# Power_Outlet-RevB.net
KiCad netlist of a schematic drawn in EAGLE
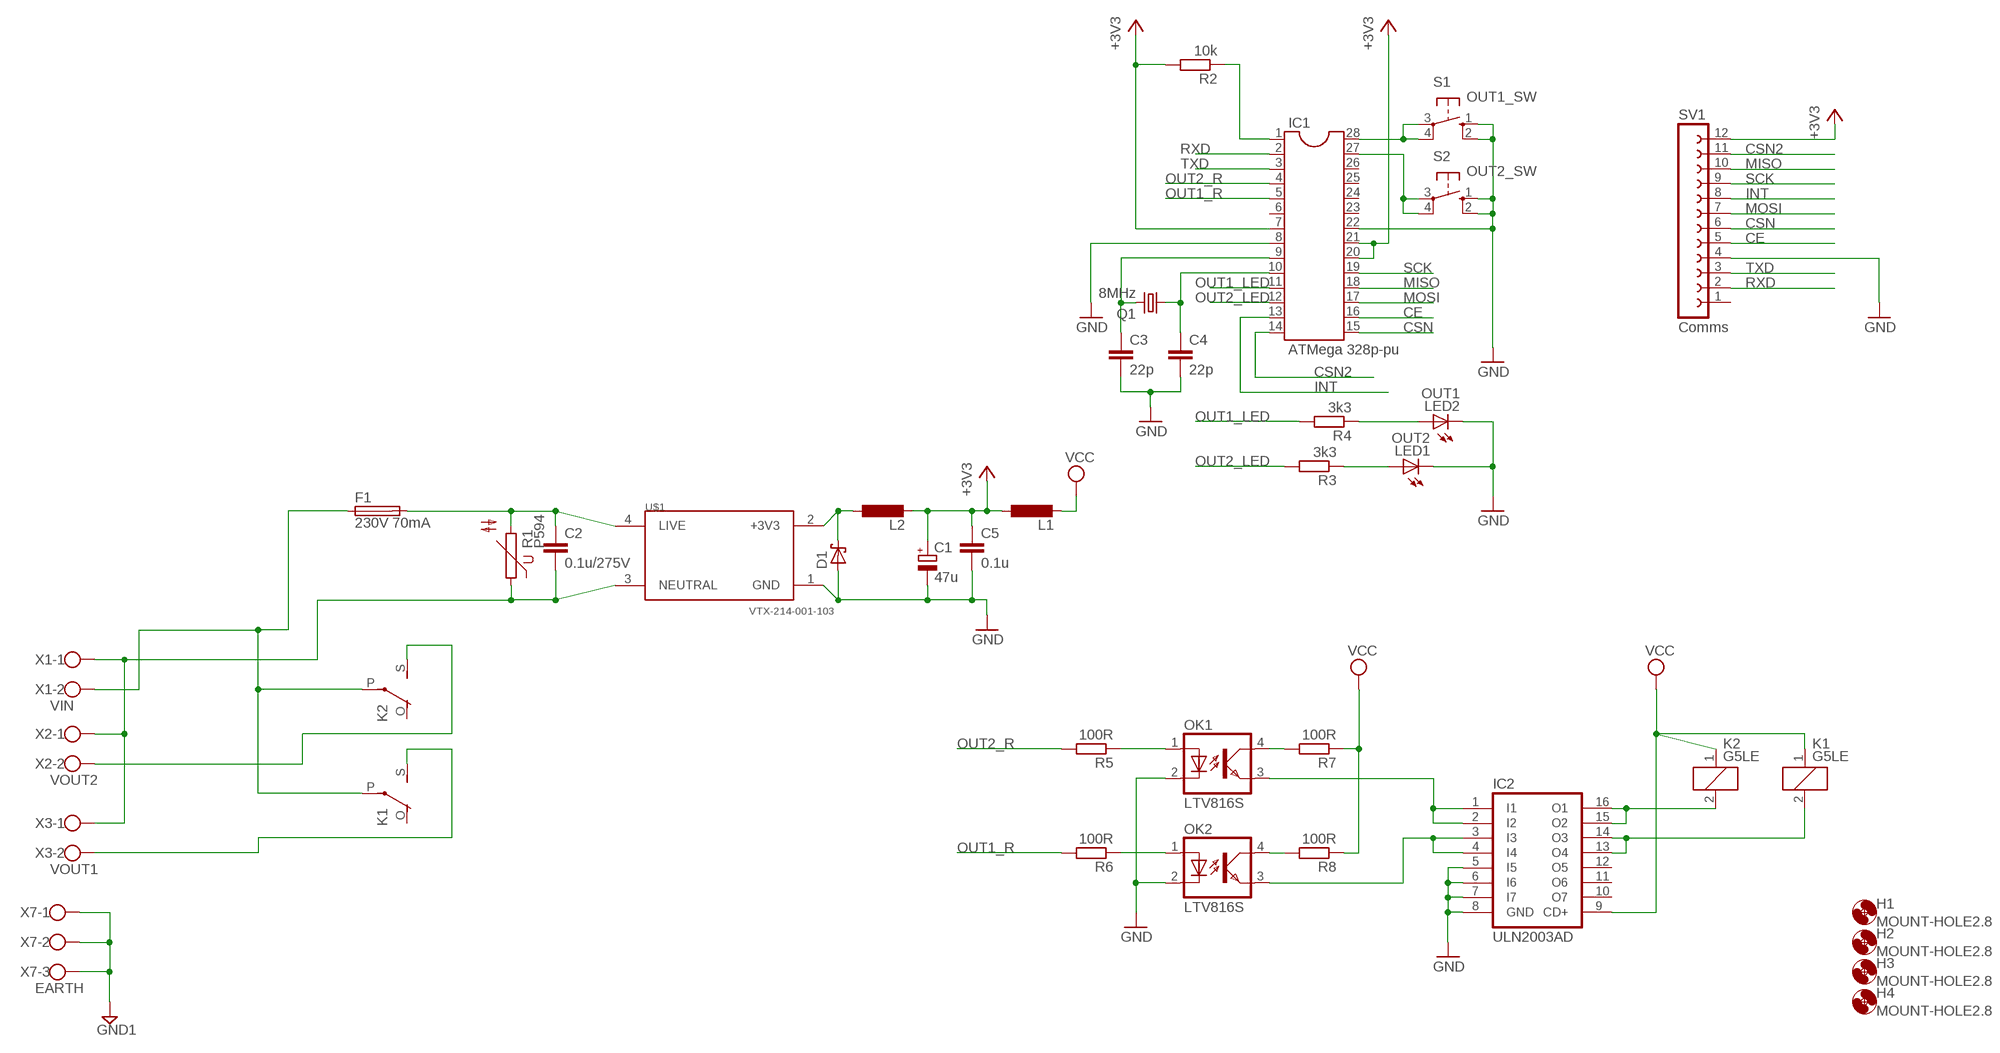
[diagram p0: schematic, sheet 1]

(export (version "E")
  (design (tool "Eeschema 10.0.6"))
  (components
    (comp (ref "C1")
      (value "47u")
      (footprint "eagle-import:E2,5-6E")
      (libsource (lib "eagle-import") (part "CPOL-EUE2,5-6E"))
    )
    (comp (ref "C2")
      (value "0.1u/275V")
      (footprint "eagle-import:C150-054X183")
      (libsource (lib "eagle-import") (part "C-EU150-054X183"))
    )
    (comp (ref "C3")
      (value "22p")
      (footprint "eagle-import:C1206K")
      (libsource (lib "eagle-import") (part "C-EUC1206K"))
    )
    (comp (ref "C4")
      (value "22p")
      (footprint "eagle-import:C1206K")
      (libsource (lib "eagle-import") (part "C-EUC1206K"))
    )
    (comp (ref "C5")
      (value "0.1u")
      (footprint "eagle-import:C1206K")
      (libsource (lib "eagle-import") (part "C-EUC1206K"))
    )
    (comp (ref "D1")
      (value "SCHOTTKY-DIODESMC")
      (footprint "eagle-import:SMC")
      (libsource (lib "eagle-import") (part "SCHOTTKY-DIODESMC"))
    )
    (comp (ref "F1")
      (value "230V 70mA")
      (footprint "eagle-import:SH22,5A")
      (libsource (lib "eagle-import") (part "FUSESH22,5A"))
    )
    (comp (ref "H1")
      (value "MOUNT-HOLE2.8")
      (footprint "eagle-import:2,8")
      (libsource (lib "eagle-import") (part "MOUNT-HOLE2.8"))
    )
    (comp (ref "H2")
      (value "MOUNT-HOLE2.8")
      (footprint "eagle-import:2,8")
      (libsource (lib "eagle-import") (part "MOUNT-HOLE2.8"))
    )
    (comp (ref "H3")
      (value "MOUNT-HOLE2.8")
      (footprint "eagle-import:2,8")
      (libsource (lib "eagle-import") (part "MOUNT-HOLE2.8"))
    )
    (comp (ref "H4")
      (value "MOUNT-HOLE2.8")
      (footprint "eagle-import:2,8")
      (libsource (lib "eagle-import") (part "MOUNT-HOLE2.8"))
    )
    (comp (ref "IC1")
      (value "ATMega 328p-pu")
      (footprint "eagle-import:DIL28-3")
      (libsource (lib "eagle-import") (part "DIL28-3"))
    )
    (comp (ref "IC2")
      (value "ULN2003AD")
      (footprint "eagle-import:SO16")
      (libsource (lib "eagle-import") (part "ULN2003AD"))
    )
    (comp (ref "K1")
      (value "G5LE")
      (footprint "eagle-import:G5LE")
      (libsource (lib "eagle-import") (part "G5LE"))
    )
    (comp (ref "K2")
      (value "G5LE")
      (footprint "eagle-import:G5LE")
      (libsource (lib "eagle-import") (part "G5LE"))
    )
    (comp (ref "L1")
      (value "L-EUL3225P")
      (footprint "eagle-import:L3225P")
      (libsource (lib "eagle-import") (part "L-EUL3225P"))
    )
    (comp (ref "L2")
      (value "L-EUL3225P")
      (footprint "eagle-import:L3225P")
      (libsource (lib "eagle-import") (part "L-EUL3225P"))
    )
    (comp (ref "LED1")
      (value "OUT2")
      (footprint "eagle-import:LED5MM")
      (libsource (lib "eagle-import") (part "LED5MM"))
    )
    (comp (ref "LED2")
      (value "OUT1")
      (footprint "eagle-import:LED5MM")
      (libsource (lib "eagle-import") (part "LED5MM"))
    )
    (comp (ref "OK1")
      (value "LTV816S")
      (footprint "eagle-import:DIL4-SMD")
      (libsource (lib "eagle-import") (part "LTV816S"))
    )
    (comp (ref "OK2")
      (value "LTV816S")
      (footprint "eagle-import:DIL4-SMD")
      (libsource (lib "eagle-import") (part "LTV816S"))
    )
    (comp (ref "Q1")
      (value "8MHz")
      (footprint "eagle-import:HC49_S")
      (libsource (lib "eagle-import") (part "CRYSTALHC49S"))
    )
    (comp (ref "R1")
      (value "P594")
      (footprint "eagle-import:P594")
      (libsource (lib "eagle-import") (part "P594"))
    )
    (comp (ref "R2")
      (value "10k")
      (footprint "eagle-import:R1206W")
      (libsource (lib "eagle-import") (part "R-EU_R1206W"))
    )
    (comp (ref "R3")
      (value "3k3")
      (footprint "eagle-import:R1206W")
      (libsource (lib "eagle-import") (part "R-EU_R1206W"))
    )
    (comp (ref "R4")
      (value "3k3")
      (footprint "eagle-import:R1206W")
      (libsource (lib "eagle-import") (part "R-EU_R1206W"))
    )
    (comp (ref "R5")
      (value "100R")
      (footprint "eagle-import:R1206W")
      (libsource (lib "eagle-import") (part "R-EU_R1206W"))
    )
    (comp (ref "R6")
      (value "100R")
      (footprint "eagle-import:R1206W")
      (libsource (lib "eagle-import") (part "R-EU_R1206W"))
    )
    (comp (ref "R7")
      (value "100R")
      (footprint "eagle-import:R1206W")
      (libsource (lib "eagle-import") (part "R-EU_R1206W"))
    )
    (comp (ref "R8")
      (value "100R")
      (footprint "eagle-import:R1206W")
      (libsource (lib "eagle-import") (part "R-EU_R1206W"))
    )
    (comp (ref "S1")
      (value "OUT1_SW")
      (footprint "eagle-import:B3F-40XX")
      (fields (field (name "MF") "OMRON COMPONENTS USA") (field (name "MPN") "B3F-4000"))
      (libsource (lib "eagle-import") (part "40-XX"))
    )
    (comp (ref "S2")
      (value "OUT2_SW")
      (footprint "eagle-import:B3F-40XX")
      (fields (field (name "MF") "OMRON COMPONENTS USA") (field (name "MPN") "B3F-4000"))
      (libsource (lib "eagle-import") (part "40-XX"))
    )
    (comp (ref "SV1")
      (value "Comms")
      (footprint "eagle-import:FE12W")
      (libsource (lib "eagle-import") (part "FE12W"))
    )
    (comp (ref "U$1")
      (value "VTX-214-001-103")
      (footprint "eagle-import:VTX214001103")
      (libsource (lib "eagle-import") (part "VTX-214-001-103"))
    )
    (comp (ref "X1")
      (value "VIN")
      (footprint "eagle-import:W237-102")
      (fields (field (name "MPN") "237-102"))
      (libsource (lib "eagle-import") (part "W237-102"))
    )
    (comp (ref "X2")
      (value "VOUT2")
      (footprint "eagle-import:W237-102")
      (fields (field (name "MPN") "237-102"))
      (libsource (lib "eagle-import") (part "W237-102"))
    )
    (comp (ref "X3")
      (value "VOUT1")
      (footprint "eagle-import:W237-102")
      (fields (field (name "MPN") "237-102"))
      (libsource (lib "eagle-import") (part "W237-102"))
    )
    (comp (ref "X7")
      (value "EARTH")
      (footprint "eagle-import:W237-103")
      (fields (field (name "MPN") "237-103"))
      (libsource (lib "eagle-import") (part "W237-103"))
    )
  )
  (nets
    (net (code "1") (name "+3V3") (class "Default")
      (node (ref "C1") (pin "+") (pinfunction "+_+") (pintype "passive"))
      (node (ref "C5") (pin "1") (pinfunction "1_1") (pintype "passive"))
      (node (ref "D1") (pin "C") (pinfunction "C_C") (pintype "passive"))
      (node (ref "IC1") (pin "20") (pinfunction "20_20") (pintype "passive"))
      (node (ref "IC1") (pin "21") (pinfunction "21_21") (pintype "passive"))
      (node (ref "IC1") (pin "7") (pinfunction "7_7") (pintype "passive"))
      (node (ref "L1") (pin "1") (pinfunction "1_1") (pintype "passive"))
      (node (ref "L2") (pin "1") (pinfunction "1_1") (pintype "passive"))
      (node (ref "L2") (pin "2") (pinfunction "2_2") (pintype "passive"))
      (node (ref "R2") (pin "2") (pinfunction "2_2") (pintype "passive"))
      (node (ref "SV1") (pin "12") (pinfunction "12_12") (pintype "passive"))
      (node (ref "U$1") (pin "2") (pinfunction "+3V3_2") (pintype "power_in"))
    )
    (net (code "2") (name "/CE") (class "Default")
      (node (ref "IC1") (pin "16") (pinfunction "16_16") (pintype "passive"))
      (node (ref "SV1") (pin "5") (pinfunction "5_5") (pintype "passive"))
    )
    (net (code "3") (name "/CSN") (class "Default")
      (node (ref "IC1") (pin "15") (pinfunction "15_15") (pintype "passive"))
      (node (ref "SV1") (pin "6") (pinfunction "6_6") (pintype "passive"))
    )
    (net (code "4") (name "/CSN2") (class "Default")
      (node (ref "IC1") (pin "14") (pinfunction "14_14") (pintype "passive"))
      (node (ref "SV1") (pin "11") (pinfunction "11_11") (pintype "passive"))
    )
    (net (code "5") (name "/INT") (class "Default")
      (node (ref "IC1") (pin "13") (pinfunction "13_13") (pintype "passive"))
      (node (ref "SV1") (pin "8") (pinfunction "8_8") (pintype "passive"))
    )
    (net (code "6") (name "/MISO") (class "Default")
      (node (ref "IC1") (pin "18") (pinfunction "18_18") (pintype "passive"))
      (node (ref "SV1") (pin "10") (pinfunction "10_10") (pintype "passive"))
    )
    (net (code "7") (name "/MOSI") (class "Default")
      (node (ref "IC1") (pin "17") (pinfunction "17_17") (pintype "passive"))
      (node (ref "SV1") (pin "7") (pinfunction "7_7") (pintype "passive"))
    )
    (net (code "8") (name "/OUT1_LED") (class "Default")
      (node (ref "IC1") (pin "11") (pinfunction "11_11") (pintype "passive"))
      (node (ref "R4") (pin "2") (pinfunction "2_2") (pintype "passive"))
    )
    (net (code "9") (name "/OUT1_R") (class "Default")
      (node (ref "IC1") (pin "5") (pinfunction "5_5") (pintype "passive"))
      (node (ref "R6") (pin "2") (pinfunction "2_2") (pintype "passive"))
    )
    (net (code "10") (name "/OUT2_LED") (class "Default")
      (node (ref "IC1") (pin "12") (pinfunction "12_12") (pintype "passive"))
      (node (ref "R3") (pin "2") (pinfunction "2_2") (pintype "passive"))
    )
    (net (code "11") (name "/OUT2_R") (class "Default")
      (node (ref "IC1") (pin "4") (pinfunction "4_4") (pintype "passive"))
      (node (ref "R5") (pin "2") (pinfunction "2_2") (pintype "passive"))
    )
    (net (code "12") (name "/RXD") (class "Default")
      (node (ref "IC1") (pin "2") (pinfunction "2_2") (pintype "passive"))
      (node (ref "SV1") (pin "2") (pinfunction "2_2") (pintype "passive"))
    )
    (net (code "13") (name "/SCK") (class "Default")
      (node (ref "IC1") (pin "19") (pinfunction "19_19") (pintype "passive"))
      (node (ref "SV1") (pin "9") (pinfunction "9_9") (pintype "passive"))
    )
    (net (code "14") (name "/TXD") (class "Default")
      (node (ref "IC1") (pin "3") (pinfunction "3_3") (pintype "passive"))
      (node (ref "SV1") (pin "3") (pinfunction "3_3") (pintype "passive"))
    )
    (net (code "15") (name "GND") (class "Default")
      (node (ref "C1") (pin "-") (pinfunction "-_-") (pintype "passive"))
      (node (ref "C3") (pin "2") (pinfunction "2_2") (pintype "passive"))
      (node (ref "C4") (pin "2") (pinfunction "2_2") (pintype "passive"))
      (node (ref "C5") (pin "2") (pinfunction "2_2") (pintype "passive"))
      (node (ref "D1") (pin "A") (pinfunction "A_A") (pintype "passive"))
      (node (ref "IC1") (pin "22") (pinfunction "22_22") (pintype "passive"))
      (node (ref "IC1") (pin "8") (pinfunction "8_8") (pintype "passive"))
      (node (ref "IC2") (pin "5") (pinfunction "I5_5") (pintype "input"))
      (node (ref "IC2") (pin "6") (pinfunction "I6_6") (pintype "input"))
      (node (ref "IC2") (pin "7") (pinfunction "I7_7") (pintype "input"))
      (node (ref "IC2") (pin "8") (pinfunction "GND_8") (pintype "power_in"))
      (node (ref "LED1") (pin "K") (pinfunction "C_K") (pintype "passive"))
      (node (ref "LED2") (pin "K") (pinfunction "C_K") (pintype "passive"))
      (node (ref "OK1") (pin "2") (pinfunction "C_2") (pintype "passive"))
      (node (ref "OK2") (pin "2") (pinfunction "C_2") (pintype "passive"))
      (node (ref "S1") (pin "1") (pinfunction "S_1") (pintype "passive"))
      (node (ref "S1") (pin "2") (pinfunction "S1_2") (pintype "passive"))
      (node (ref "S2") (pin "1") (pinfunction "S_1") (pintype "passive"))
      (node (ref "S2") (pin "2") (pinfunction "S1_2") (pintype "passive"))
      (node (ref "SV1") (pin "4") (pinfunction "4_4") (pintype "passive"))
      (node (ref "U$1") (pin "1") (pinfunction "GND_1") (pintype "power_in"))
    )
    (net (code "16") (name "GND1") (class "Default")
      (node (ref "X7") (pin "1") (pinfunction "KL_1") (pintype "passive"))
      (node (ref "X7") (pin "2") (pinfunction "KL_2") (pintype "passive"))
      (node (ref "X7") (pin "3") (pinfunction "KL_3") (pintype "passive"))
    )
    (net (code "17") (name "Net-(C3-Pad1)") (class "Default")
      (node (ref "C3") (pin "1") (pinfunction "1_1") (pintype "passive"))
      (node (ref "IC1") (pin "9") (pinfunction "9_9") (pintype "passive"))
      (node (ref "Q1") (pin "2") (pinfunction "2_2") (pintype "passive"))
    )
    (net (code "18") (name "Net-(C4-Pad1)") (class "Default")
      (node (ref "C4") (pin "1") (pinfunction "1_1") (pintype "passive"))
      (node (ref "IC1") (pin "10") (pinfunction "10_10") (pintype "passive"))
      (node (ref "Q1") (pin "1") (pinfunction "1_1") (pintype "passive"))
    )
    (net (code "19") (name "Net-(IC1-Pad1)") (class "Default")
      (node (ref "IC1") (pin "1") (pinfunction "1_1") (pintype "passive"))
      (node (ref "R2") (pin "1") (pinfunction "1_1") (pintype "passive"))
    )
    (net (code "20") (name "Net-(IC2-I1)") (class "Default")
      (node (ref "IC2") (pin "1") (pinfunction "I1_1") (pintype "input"))
      (node (ref "IC2") (pin "2") (pinfunction "I2_2") (pintype "input"))
      (node (ref "OK1") (pin "3") (pinfunction "EMIT_3") (pintype "passive"))
    )
    (net (code "21") (name "Net-(IC2-I3)") (class "Default")
      (node (ref "IC2") (pin "3") (pinfunction "I3_3") (pintype "input"))
      (node (ref "IC2") (pin "4") (pinfunction "I4_4") (pintype "input"))
      (node (ref "OK2") (pin "3") (pinfunction "EMIT_3") (pintype "passive"))
    )
    (net (code "22") (name "Net-(IC2-O1)") (class "Default")
      (node (ref "IC2") (pin "15") (pinfunction "O2_15") (pintype "open_collector"))
      (node (ref "IC2") (pin "16") (pinfunction "O1_16") (pintype "open_collector"))
      (node (ref "K2") (pin "2") (pinfunction "2_2") (pintype "passive"))
    )
    (net (code "23") (name "Net-(IC2-O3)") (class "Default")
      (node (ref "IC2") (pin "13") (pinfunction "O4_13") (pintype "open_collector"))
      (node (ref "IC2") (pin "14") (pinfunction "O3_14") (pintype "open_collector"))
      (node (ref "K1") (pin "2") (pinfunction "2_2") (pintype "passive"))
    )
    (net (code "24") (name "Net-(LED1-PadA)") (class "Default")
      (node (ref "LED1") (pin "A") (pinfunction "A_A") (pintype "passive"))
      (node (ref "R3") (pin "1") (pinfunction "1_1") (pintype "passive"))
    )
    (net (code "25") (name "Net-(LED2-PadA)") (class "Default")
      (node (ref "LED2") (pin "A") (pinfunction "A_A") (pintype "passive"))
      (node (ref "R4") (pin "1") (pinfunction "1_1") (pintype "passive"))
    )
    (net (code "26") (name "Net-(OK1-A)") (class "Default")
      (node (ref "OK1") (pin "1") (pinfunction "A_1") (pintype "passive"))
      (node (ref "R5") (pin "1") (pinfunction "1_1") (pintype "passive"))
    )
    (net (code "27") (name "Net-(OK1-COL)") (class "Default")
      (node (ref "OK1") (pin "4") (pinfunction "COL_4") (pintype "passive"))
      (node (ref "R7") (pin "2") (pinfunction "2_2") (pintype "passive"))
    )
    (net (code "28") (name "Net-(OK2-A)") (class "Default")
      (node (ref "OK2") (pin "1") (pinfunction "A_1") (pintype "passive"))
      (node (ref "R6") (pin "1") (pinfunction "1_1") (pintype "passive"))
    )
    (net (code "29") (name "Net-(OK2-COL)") (class "Default")
      (node (ref "OK2") (pin "4") (pinfunction "COL_4") (pintype "passive"))
      (node (ref "R8") (pin "2") (pinfunction "2_2") (pintype "passive"))
    )
    (net (code "30") (name "Net-(S1-P)") (class "Default")
      (node (ref "IC1") (pin "28") (pinfunction "28_28") (pintype "passive"))
      (node (ref "S1") (pin "3") (pinfunction "P_3") (pintype "passive"))
      (node (ref "S1") (pin "4") (pinfunction "P1_4") (pintype "passive"))
    )
    (net (code "31") (name "Net-(S2-P)") (class "Default")
      (node (ref "IC1") (pin "27") (pinfunction "27_27") (pintype "passive"))
      (node (ref "S2") (pin "3") (pinfunction "P_3") (pintype "passive"))
      (node (ref "S2") (pin "4") (pinfunction "P1_4") (pintype "passive"))
    )
    (net (code "32") (name "Net-(U$1-LIVE)") (class "Default")
      (node (ref "C2") (pin "1") (pinfunction "1_1") (pintype "passive"))
      (node (ref "F1") (pin "2") (pinfunction "2_2") (pintype "passive"))
      (node (ref "R1") (pin "2") (pinfunction "2_2") (pintype "passive"))
      (node (ref "U$1") (pin "4") (pinfunction "LIVE_4") (pintype "input"))
    )
    (net (code "33") (name "Net-(U$1-NEUTRAL)") (class "Default")
      (node (ref "C2") (pin "2") (pinfunction "2_2") (pintype "passive"))
      (node (ref "R1") (pin "1") (pinfunction "1_1") (pintype "passive"))
      (node (ref "U$1") (pin "3") (pinfunction "NEUTRAL_3") (pintype "input"))
      (node (ref "X1") (pin "1") (pinfunction "KL_1") (pintype "passive"))
      (node (ref "X2") (pin "1") (pinfunction "KL_1") (pintype "passive"))
      (node (ref "X3") (pin "1") (pinfunction "KL_1") (pintype "passive"))
    )
    (net (code "34") (name "Net-(X1B-KL)") (class "Default")
      (node (ref "F1") (pin "1") (pinfunction "1_1") (pintype "passive"))
      (node (ref "K1") (pin "P") (pinfunction "P_P") (pintype "passive"))
      (node (ref "K2") (pin "P") (pinfunction "P_P") (pintype "passive"))
      (node (ref "X1") (pin "2") (pinfunction "KL_2") (pintype "passive"))
    )
    (net (code "35") (name "Net-(X2B-KL)") (class "Default")
      (node (ref "K2") (pin "S") (pinfunction "S_S") (pintype "passive"))
      (node (ref "X2") (pin "2") (pinfunction "KL_2") (pintype "passive"))
    )
    (net (code "36") (name "Net-(X3B-KL)") (class "Default")
      (node (ref "K1") (pin "S") (pinfunction "S_S") (pintype "passive"))
      (node (ref "X3") (pin "2") (pinfunction "KL_2") (pintype "passive"))
    )
    (net (code "37") (name "VCC") (class "Default")
      (node (ref "IC2") (pin "9") (pinfunction "CD+_9") (pintype "passive"))
      (node (ref "K1") (pin "1") (pinfunction "1_1") (pintype "passive"))
      (node (ref "K2") (pin "1") (pinfunction "1_1") (pintype "passive"))
      (node (ref "L1") (pin "2") (pinfunction "2_2") (pintype "passive"))
      (node (ref "R7") (pin "1") (pinfunction "1_1") (pintype "passive"))
      (node (ref "R8") (pin "1") (pinfunction "1_1") (pintype "passive"))
    )
    (net (code "38") (name "unconnected-(IC1-Pad6)") (class "Default")
      (node (ref "IC1") (pin "6") (pinfunction "6_6") (pintype "passive"))
    )
    (net (code "39") (name "unconnected-(IC1-Pad23)") (class "Default")
      (node (ref "IC1") (pin "23") (pinfunction "23_23") (pintype "passive"))
    )
    (net (code "40") (name "unconnected-(IC1-Pad24)") (class "Default")
      (node (ref "IC1") (pin "24") (pinfunction "24_24") (pintype "passive"))
    )
    (net (code "41") (name "unconnected-(IC1-Pad25)") (class "Default")
      (node (ref "IC1") (pin "25") (pinfunction "25_25") (pintype "passive"))
    )
    (net (code "42") (name "unconnected-(IC1-Pad26)") (class "Default")
      (node (ref "IC1") (pin "26") (pinfunction "26_26") (pintype "passive"))
    )
    (net (code "43") (name "unconnected-(IC2-O5-Pad12)") (class "Default")
      (node (ref "IC2") (pin "12") (pinfunction "O5_12") (pintype "open_collector"))
    )
    (net (code "44") (name "unconnected-(IC2-O6-Pad11)") (class "Default")
      (node (ref "IC2") (pin "11") (pinfunction "O6_11") (pintype "open_collector"))
    )
    (net (code "45") (name "unconnected-(IC2-O7-Pad10)") (class "Default")
      (node (ref "IC2") (pin "10") (pinfunction "O7_10") (pintype "open_collector"))
    )
    (net (code "46") (name "unconnected-(K1-PadO)") (class "Default")
      (node (ref "K1") (pin "O") (pinfunction "O_O") (pintype "passive"))
    )
    (net (code "47") (name "unconnected-(K2-PadO)") (class "Default")
      (node (ref "K2") (pin "O") (pinfunction "O_O") (pintype "passive"))
    )
    (net (code "48") (name "unconnected-(SV1-Pad1)") (class "Default")
      (node (ref "SV1") (pin "1") (pinfunction "1_1") (pintype "passive"))
    )
  )
)
